# USB_Isolator.net
KiCad netlist of a schematic drawn in Altium Designer
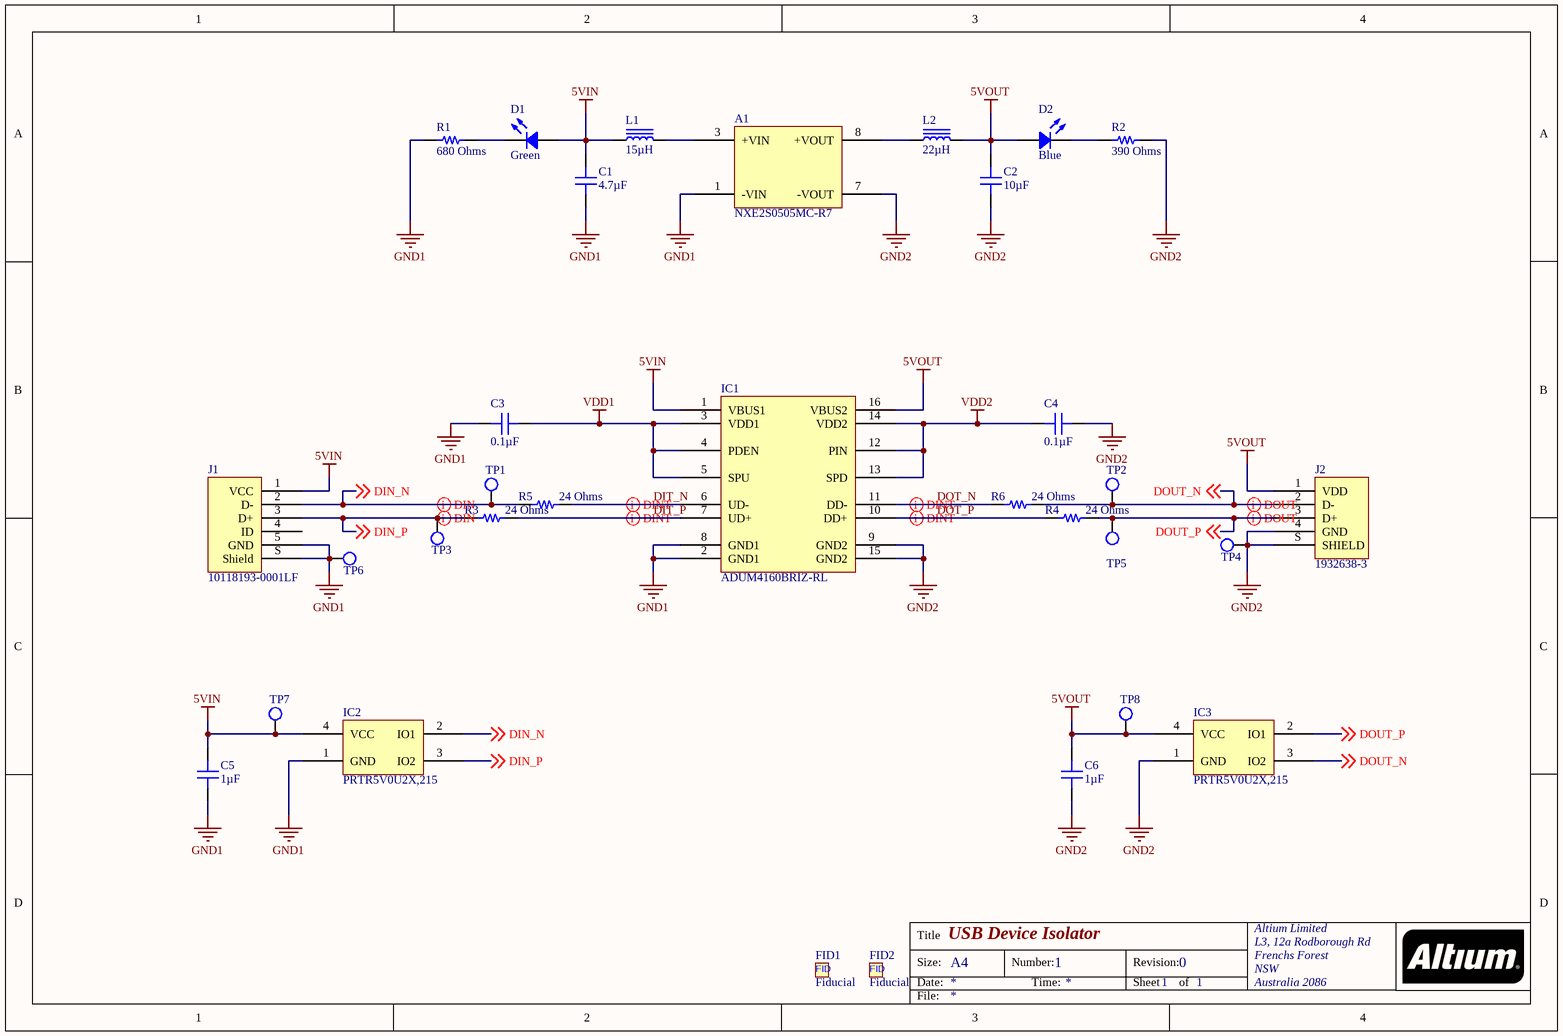
[diagram p0: USB Isolator.SchDoc]

(export (version "E")
  (design (tool "Eeschema 10.0.6"))
  (components
    (comp (ref "A1")
      (value "NXE2S0505MC-R7")
      (footprint "MURATA NXE")
      (description "DC DC CONVERTER 5V 2W")
      (fields
        (field (name "PART NUMBER") "NXE2S0505MC-R7")
        (field (name "MANUFACTURER") "Murata Power Solutions Inc.")
      )
      (libsource (lib "Celestial Altium Library - altium_library") (part "MURATA NXE"))
    )
    (comp (ref "C1")
      (value "4.7µF")
      (footprint "CAP 1206_3216 - 1.8MM")
      (description "CAP CER 4.7UF 16V X7R 1206")
      (fields
        (field (name "PART NUMBER") "CL31B475KOHNNNE")
        (field (name "MANUFACTURER") "Samsung Electro-Mechanics")
      )
      (libsource (lib "Celestial Altium Library - altium_library") (part "Capacitor"))
    )
    (comp (ref "C2")
      (value "10µF")
      (footprint "CAP 1206_3216 - 1.8MM")
      (description "CAP CER 10UF 16V X7R 1206")
      (fields
        (field (name "PART NUMBER") "CL31B106MOHNNNE")
        (field (name "MANUFACTURER") "Samsung Electro-Mechanics")
      )
      (libsource (lib "Celestial Altium Library - altium_library") (part "Capacitor"))
    )
    (comp (ref "C3")
      (value "0.1µF")
      (footprint "CAP 0603_1608")
      (description "CAP CER 0.1UF 50V X7R 0603")
      (fields
        (field (name "PART NUMBER") "CL10B104KB8NNNL")
        (field (name "MANUFACTURER") "Samsung Electro-Mechanics")
      )
      (libsource (lib "Celestial Altium Library - altium_library") (part "Capacitor"))
    )
    (comp (ref "C4")
      (value "0.1µF")
      (footprint "CAP 0603_1608")
      (description "CAP CER 0.1UF 50V X7R 0603")
      (fields
        (field (name "PART NUMBER") "CL10B104KB8NNNL")
        (field (name "MANUFACTURER") "Samsung Electro-Mechanics")
      )
      (libsource (lib "Celestial Altium Library - altium_library") (part "Capacitor"))
    )
    (comp (ref "C5")
      (value "1µF")
      (footprint "CAP 0603_1608")
      (description "CAP CER 1UF 25V X5R 0603")
      (fields (field (name "PART NUMBER") "CC0603KRX5R8BB105") (field (name "MANUFACTURER") "Yageo"))
      (libsource (lib "Celestial Altium Library - altium_library") (part "Capacitor"))
    )
    (comp (ref "C6")
      (value "1µF")
      (footprint "CAP 0603_1608")
      (description "CAP CER 1UF 25V X5R 0603")
      (fields (field (name "PART NUMBER") "CC0603KRX5R8BB105") (field (name "MANUFACTURER") "Yageo"))
      (libsource (lib "Celestial Altium Library - altium_library") (part "Capacitor"))
    )
    (comp (ref "D1")
      (value "Green")
      (footprint "LED 0603_1608 GREEN")
      (description "LED GREEN CLEAR SMD")
      (fields (field (name "PART NUMBER") "LTST-C191KGKT") (field (name "MANUFACTURER") "Lite-On Inc."))
      (libsource (lib "Celestial Altium Library - altium_library") (part "LED"))
    )
    (comp (ref "D2")
      (value "Blue")
      (footprint "LED 0603_1608 BLUE")
      (description "LED BLUE CLEAR SMD")
      (fields (field (name "PART NUMBER") "LTST-C194TBKT") (field (name "MANUFACTURER") "Lite-On Inc."))
      (libsource (lib "Celestial Altium Library - altium_library") (part "LED"))
    )
    (comp (ref "FID1")
      (value "Fiducial")
      (footprint "Fiducial-1mm")
      (libsource (lib "CelestialUseful") (part "Fiducial"))
    )
    (comp (ref "FID2")
      (value "Fiducial")
      (footprint "Fiducial-1mm")
      (libsource (lib "CelestialUseful") (part "Fiducial"))
    )
    (comp (ref "IC1")
      (value "ADUM4160BRIZ-RL")
      (footprint "ANALOG DEV SOIC-16 RI-16-1")
      (description "DGTL ISOLATOR 5KV 2CH USB 16SOIC")
      (fields
        (field (name "PART NUMBER") "ADUM4160BRIZ-RL")
        (field (name "MANUFACTURER") "Analog Devices Inc.")
      )
      (libsource (lib "Celestial Altium Library - altium_library") (part "ANALOG DEVICES ADUM4160BRIZ-RL"))
    )
    (comp (ref "IC2")
      (value "PRTR5V0U2X,215")
      (footprint "SOT143B")
      (description "TVS DIODE 5.5V SOT143B")
      (fields (field (name "PART NUMBER") "PRTR5V0U2X,215") (field (name "MANUFACTURER") "Nexperia USA Inc."))
      (libsource (lib "Celestial Altium Library - altium_library") (part "NXP PRTR5V0U2X"))
    )
    (comp (ref "IC3")
      (value "PRTR5V0U2X,215")
      (footprint "SOT143B")
      (description "TVS DIODE 5.5V SOT143B")
      (fields (field (name "PART NUMBER") "PRTR5V0U2X,215") (field (name "MANUFACTURER") "Nexperia USA Inc."))
      (libsource (lib "Celestial Altium Library - altium_library") (part "NXP PRTR5V0U2X"))
    )
    (comp (ref "J1")
      (value "10118193-0001LF")
      (footprint "FCI USB 10118193-0001LF")
      (description "CONN RCPT USB2.0 MICRO B SMD R/A")
      (fields
        (field (name "PART NUMBER") "10118193-0001LF")
        (field (name "MANUFACTURER") "Amphenol ICC (FCI)")
      )
      (libsource (lib "Celestial Altium Library - altium_library") (part "USB 2.0 Type B Micro"))
    )
    (comp (ref "J2")
      (value "1932638-3")
      (footprint "TE 1932638-3 USB2.0A")
      (description "CONN RCPT USB2.0 TYPEA 4P SMD RA")
      (fields
        (field (name "PART NUMBER") "1932638-3")
        (field (name "MANUFACTURER") "TE Connectivity AMP Connectors")
      )
      (libsource (lib "Celestial Altium Library - altium_library") (part "TE 1932638-3"))
    )
    (comp (ref "L1")
      (value "15µH")
      (footprint "TDK VLCF4028-2")
      (description "FIXED IND 15UH 880MA 170 MOHM")
      (fields
        (field (name "PART NUMBER") "VLCF4028T-150MR88-2")
        (field (name "MANUFACTURER") "TDK Corporation")
      )
      (libsource (lib "Celestial Altium Library - altium_library") (part "Inductor"))
    )
    (comp (ref "L2")
      (value "22µH")
      (footprint "TDK VLCF4024-2")
      (description "FIXED IND 22UH 650MA 332 MOHM")
      (fields
        (field (name "PART NUMBER") "VLCF4024T-220MR65-2")
        (field (name "MANUFACTURER") "TDK Corporation")
      )
      (libsource (lib "Celestial Altium Library - altium_library") (part "Inductor"))
    )
    (comp (ref "R1")
      (value "680 Ohms")
      (footprint "RES 0603_1608")
      (description "RES SMD 680 OHM 5% 1/10W 0603")
      (fields (field (name "PART NUMBER") "CR0603-JW-681ELF") (field (name "MANUFACTURER") "Bourns Inc."))
      (libsource (lib "Celestial Altium Library - altium_library") (part "Resistor"))
    )
    (comp (ref "R2")
      (value "390 Ohms")
      (footprint "RES 0603_1608")
      (description "RES SMD 390 OHM 1% 1/10W 0603")
      (fields (field (name "PART NUMBER") "CRCW0603390RFKEA") (field (name "MANUFACTURER") "Vishay Dale"))
      (libsource (lib "Celestial Altium Library - altium_library") (part "Resistor"))
    )
    (comp (ref "R3")
      (value "24 Ohms")
      (footprint "RES 0603_1608")
      (description "RES SMD 24 OHM 1% 1/10W 0603")
      (fields (field (name "PART NUMBER") "CRCW060324R0FKEA") (field (name "MANUFACTURER") "Vishay Dale"))
      (libsource (lib "Celestial Altium Library - altium_library") (part "Resistor"))
    )
    (comp (ref "R4")
      (value "24 Ohms")
      (footprint "RES 0603_1608")
      (description "RES SMD 24 OHM 1% 1/10W 0603")
      (fields (field (name "PART NUMBER") "CRCW060324R0FKEA") (field (name "MANUFACTURER") "Vishay Dale"))
      (libsource (lib "Celestial Altium Library - altium_library") (part "Resistor"))
    )
    (comp (ref "R5")
      (value "24 Ohms")
      (footprint "RES 0603_1608")
      (description "RES SMD 24 OHM 1% 1/10W 0603")
      (fields (field (name "PART NUMBER") "CRCW060324R0FKEA") (field (name "MANUFACTURER") "Vishay Dale"))
      (libsource (lib "Celestial Altium Library - altium_library") (part "Resistor"))
    )
    (comp (ref "R6")
      (value "24 Ohms")
      (footprint "RES 0603_1608")
      (description "RES SMD 24 OHM 1% 1/10W 0603")
      (fields (field (name "PART NUMBER") "CRCW060324R0FKEA") (field (name "MANUFACTURER") "Vishay Dale"))
      (libsource (lib "Celestial Altium Library - altium_library") (part "Resistor"))
    )
    (comp (ref "TP1")
      (value "Test Point")
      (footprint "TestPoint-1.5mm")
      (libsource (lib "CelestialUseful") (part "Test Point"))
    )
    (comp (ref "TP2")
      (value "Test Point")
      (footprint "TestPoint-1.5mm")
      (libsource (lib "CelestialUseful") (part "Test Point"))
    )
    (comp (ref "TP3")
      (value "Test Point")
      (footprint "TestPoint-1.5mm")
      (libsource (lib "CelestialUseful") (part "Test Point"))
    )
    (comp (ref "TP4")
      (value "Test Point")
      (footprint "TestPoint-1.5mm")
      (libsource (lib "CelestialUseful") (part "Test Point"))
    )
    (comp (ref "TP5")
      (value "Test Point")
      (footprint "TestPoint-1.5mm")
      (libsource (lib "CelestialUseful") (part "Test Point"))
    )
    (comp (ref "TP6")
      (value "Test Point")
      (footprint "TestPoint-1.5mm")
      (libsource (lib "CelestialUseful") (part "Test Point"))
    )
    (comp (ref "TP7")
      (value "Test Point")
      (footprint "TestPoint-1.5mm")
      (libsource (lib "CelestialUseful") (part "Test Point"))
    )
    (comp (ref "TP8")
      (value "Test Point")
      (footprint "TestPoint-1.5mm")
      (libsource (lib "CelestialUseful") (part "Test Point"))
    )
  )
  (nets
    (net (code "1") (name "/DIT_N") (class "Default")
      (node (ref "IC1") (pin "6") (pinfunction "UD-_6") (pintype "passive"))
      (node (ref "R5") (pin "1") (pinfunction "1_1") (pintype "passive"))
    )
    (net (code "2") (name "/DIT_P") (class "Default")
      (node (ref "IC1") (pin "7") (pinfunction "UD+_7") (pintype "passive"))
      (node (ref "R3") (pin "1") (pinfunction "1_1") (pintype "passive"))
    )
    (net (code "3") (name "/DOT_N") (class "Default")
      (node (ref "IC1") (pin "11") (pinfunction "DD-_11") (pintype "passive"))
      (node (ref "R6") (pin "2") (pinfunction "2_2") (pintype "passive"))
    )
    (net (code "4") (name "/DOT_P") (class "Default")
      (node (ref "IC1") (pin "10") (pinfunction "DD+_10") (pintype "passive"))
      (node (ref "R4") (pin "2") (pinfunction "2_2") (pintype "passive"))
    )
    (net (code "5") (name "5VIN") (class "Default")
      (node (ref "C1") (pin "1") (pinfunction "1_1") (pintype "passive"))
      (node (ref "C5") (pin "1") (pinfunction "1_1") (pintype "passive"))
      (node (ref "D1") (pin "1") (pinfunction "1_1") (pintype "passive"))
      (node (ref "IC1") (pin "1") (pinfunction "VBUS1_1") (pintype "passive"))
      (node (ref "IC2") (pin "4") (pinfunction "VCC_4") (pintype "passive"))
      (node (ref "J1") (pin "1") (pinfunction "VCC_1") (pintype "passive"))
      (node (ref "L1") (pin "1") (pinfunction "1_1") (pintype "passive"))
      (node (ref "TP7") (pin "1") (pinfunction "TP_1") (pintype "passive"))
    )
    (net (code "6") (name "5VOUT") (class "Default")
      (node (ref "C2") (pin "1") (pinfunction "1_1") (pintype "passive"))
      (node (ref "C6") (pin "1") (pinfunction "1_1") (pintype "passive"))
      (node (ref "D2") (pin "1") (pinfunction "1_1") (pintype "passive"))
      (node (ref "IC1") (pin "16") (pinfunction "VBUS2_16") (pintype "passive"))
      (node (ref "IC3") (pin "4") (pinfunction "VCC_4") (pintype "passive"))
      (node (ref "J2") (pin "1") (pinfunction "VDD_1") (pintype "passive"))
      (node (ref "L2") (pin "2") (pinfunction "2_2") (pintype "passive"))
      (node (ref "TP8") (pin "1") (pinfunction "TP_1") (pintype "passive"))
    )
    (net (code "7") (name "DIN_N") (class "Default")
      (node (ref "IC2") (pin "2") (pinfunction "IO1_2") (pintype "passive"))
      (node (ref "J1") (pin "2") (pinfunction "D-_2") (pintype "passive"))
      (node (ref "R5") (pin "2") (pinfunction "2_2") (pintype "passive"))
      (node (ref "TP1") (pin "1") (pinfunction "TP_1") (pintype "passive"))
    )
    (net (code "8") (name "DIN_P") (class "Default")
      (node (ref "IC2") (pin "3") (pinfunction "IO2_3") (pintype "passive"))
      (node (ref "J1") (pin "3") (pinfunction "D+_3") (pintype "passive"))
      (node (ref "R3") (pin "2") (pinfunction "2_2") (pintype "passive"))
      (node (ref "TP3") (pin "1") (pinfunction "TP_1") (pintype "passive"))
    )
    (net (code "9") (name "DOUT_N") (class "Default")
      (node (ref "IC3") (pin "3") (pinfunction "IO2_3") (pintype "passive"))
      (node (ref "J2") (pin "2") (pinfunction "D-_2") (pintype "passive"))
      (node (ref "R6") (pin "1") (pinfunction "1_1") (pintype "passive"))
      (node (ref "TP2") (pin "1") (pinfunction "TP_1") (pintype "passive"))
    )
    (net (code "10") (name "DOUT_P") (class "Default")
      (node (ref "IC3") (pin "2") (pinfunction "IO1_2") (pintype "passive"))
      (node (ref "J2") (pin "3") (pinfunction "D+_3") (pintype "passive"))
      (node (ref "R4") (pin "1") (pinfunction "1_1") (pintype "passive"))
      (node (ref "TP5") (pin "1") (pinfunction "TP_1") (pintype "passive"))
    )
    (net (code "11") (name "GND1") (class "Default")
      (node (ref "A1") (pin "1") (pinfunction "-VIN_1") (pintype "passive"))
      (node (ref "C1") (pin "2") (pinfunction "2_2") (pintype "passive"))
      (node (ref "C3") (pin "1") (pinfunction "1_1") (pintype "passive"))
      (node (ref "C5") (pin "2") (pinfunction "2_2") (pintype "passive"))
      (node (ref "IC1") (pin "2") (pinfunction "GND1_2") (pintype "passive"))
      (node (ref "IC1") (pin "8") (pinfunction "GND1_8") (pintype "passive"))
      (node (ref "IC2") (pin "1") (pinfunction "GND_1") (pintype "passive"))
      (node (ref "J1") (pin "5") (pinfunction "GND_5") (pintype "passive"))
      (node (ref "J1") (pin "S") (pinfunction "Shield_S") (pintype "passive"))
      (node (ref "R1") (pin "1") (pinfunction "1_1") (pintype "passive"))
      (node (ref "TP6") (pin "1") (pinfunction "TP_1") (pintype "passive"))
    )
    (net (code "12") (name "GND2") (class "Default")
      (node (ref "A1") (pin "7") (pinfunction "-VOUT_7") (pintype "passive"))
      (node (ref "C2") (pin "2") (pinfunction "2_2") (pintype "passive"))
      (node (ref "C4") (pin "1") (pinfunction "1_1") (pintype "passive"))
      (node (ref "C6") (pin "2") (pinfunction "2_2") (pintype "passive"))
      (node (ref "IC1") (pin "15") (pinfunction "GND2_15") (pintype "passive"))
      (node (ref "IC1") (pin "9") (pinfunction "GND2_9") (pintype "passive"))
      (node (ref "IC3") (pin "1") (pinfunction "GND_1") (pintype "passive"))
      (node (ref "J2") (pin "4") (pinfunction "GND_4") (pintype "passive"))
      (node (ref "J2") (pin "S") (pinfunction "SHIELD_S") (pintype "passive"))
      (node (ref "R2") (pin "2") (pinfunction "2_2") (pintype "passive"))
      (node (ref "TP4") (pin "1") (pinfunction "TP_1") (pintype "passive"))
    )
    (net (code "13") (name "Net-(A1-+VIN)") (class "Default")
      (node (ref "A1") (pin "3") (pinfunction "+VIN_3") (pintype "passive"))
      (node (ref "L1") (pin "2") (pinfunction "2_2") (pintype "passive"))
    )
    (net (code "14") (name "Net-(A1-+VOUT)") (class "Default")
      (node (ref "A1") (pin "8") (pinfunction "+VOUT_8") (pintype "passive"))
      (node (ref "L2") (pin "1") (pinfunction "1_1") (pintype "passive"))
    )
    (net (code "15") (name "Net-(D1-Pad2)") (class "Default")
      (node (ref "D1") (pin "2") (pinfunction "2_2") (pintype "passive"))
      (node (ref "R1") (pin "2") (pinfunction "2_2") (pintype "passive"))
    )
    (net (code "16") (name "Net-(D2-Pad2)") (class "Default")
      (node (ref "D2") (pin "2") (pinfunction "2_2") (pintype "passive"))
      (node (ref "R2") (pin "1") (pinfunction "1_1") (pintype "passive"))
    )
    (net (code "17") (name "VDD1") (class "Default")
      (node (ref "C3") (pin "2") (pinfunction "2_2") (pintype "passive"))
      (node (ref "IC1") (pin "3") (pinfunction "VDD1_3") (pintype "passive"))
      (node (ref "IC1") (pin "4") (pinfunction "PDEN_4") (pintype "passive"))
      (node (ref "IC1") (pin "5") (pinfunction "SPU_5") (pintype "passive"))
    )
    (net (code "18") (name "VDD2") (class "Default")
      (node (ref "C4") (pin "2") (pinfunction "2_2") (pintype "passive"))
      (node (ref "IC1") (pin "12") (pinfunction "PIN_12") (pintype "passive"))
      (node (ref "IC1") (pin "13") (pinfunction "SPD_13") (pintype "passive"))
      (node (ref "IC1") (pin "14") (pinfunction "VDD2_14") (pintype "passive"))
    )
    (net (code "19") (name "unconnected-(J1-ID-Pad4)") (class "Default")
      (node (ref "J1") (pin "4") (pinfunction "ID_4") (pintype "passive"))
    )
  )
)
